# generic_maxi_speed_1.net
KiCad netlist of a schematic drawn in EAGLE
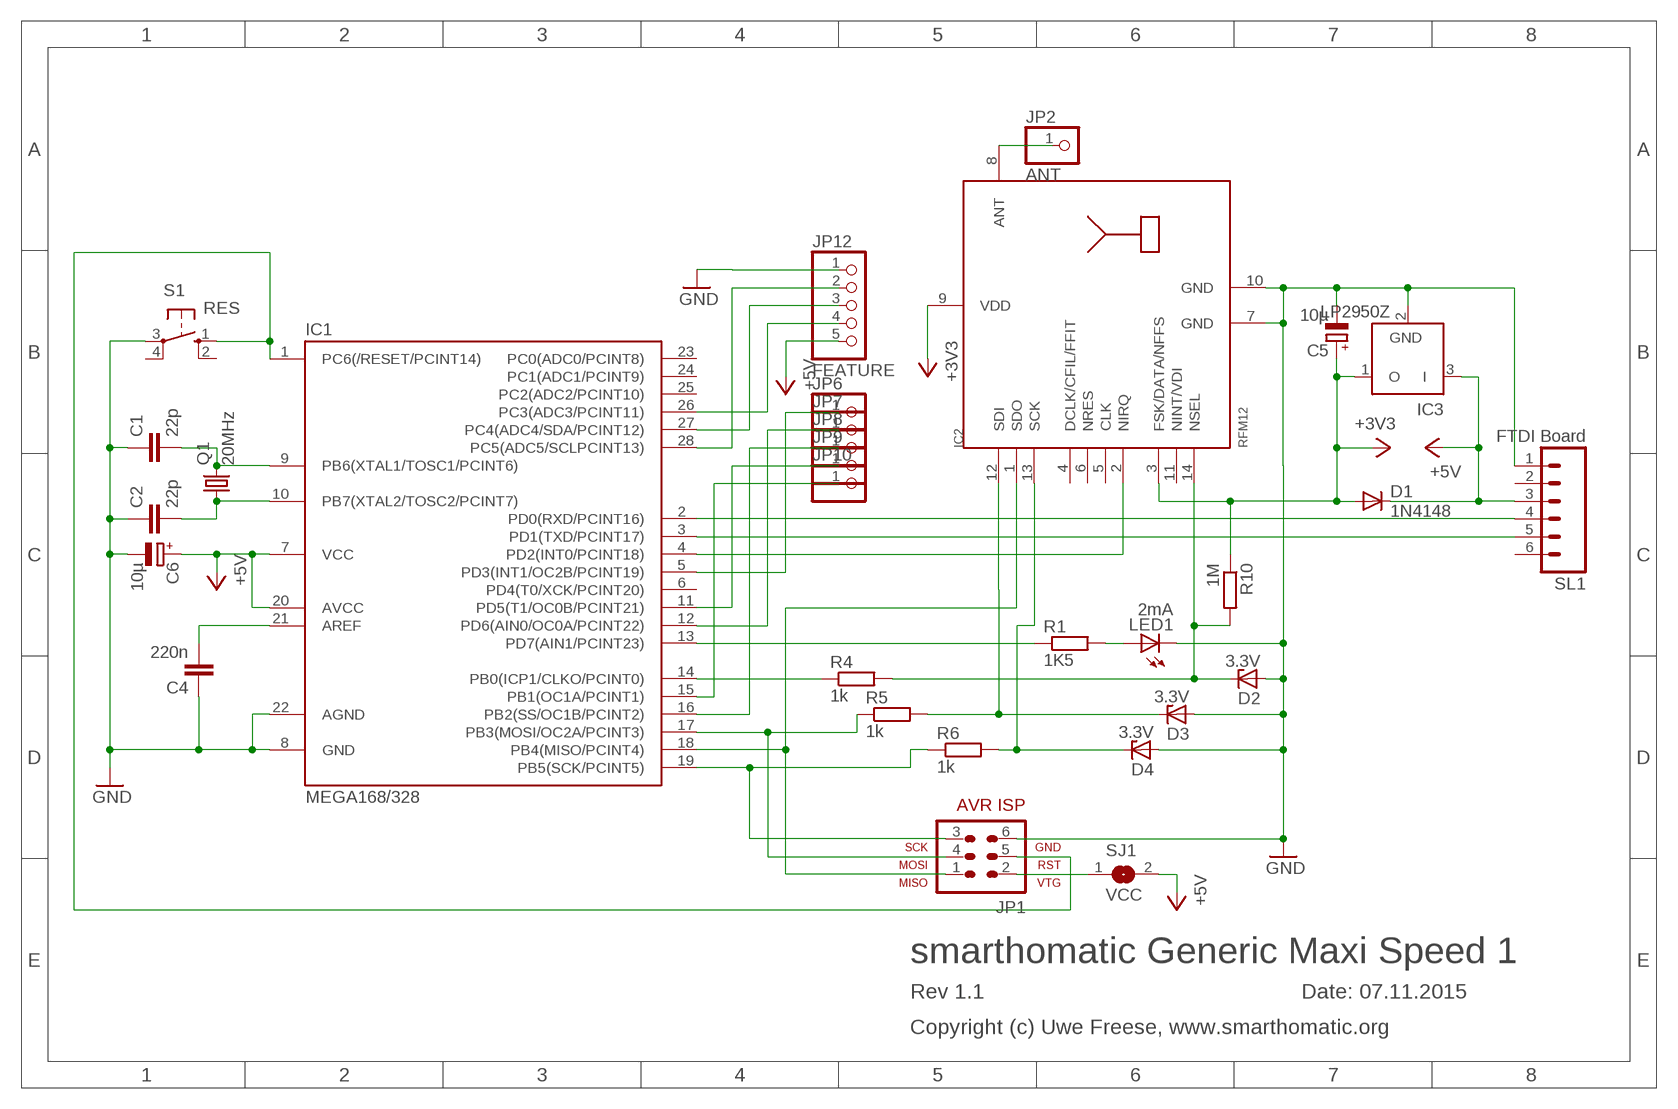
[diagram p0: schematic, sheet 1]

(export (version "E")
  (design (tool "Eeschema 10.0.6"))
  (components
    (comp (ref "C1")
      (value "22p")
      (footprint "eagle-import:C025-024X044")
      (libsource (lib "eagle-import") (part "C-EU025-024X044"))
    )
    (comp (ref "C2")
      (value "22p")
      (footprint "eagle-import:C025-024X044")
      (libsource (lib "eagle-import") (part "C-EU025-024X044"))
    )
    (comp (ref "C4")
      (value "220n")
      (footprint "eagle-import:C025-030X050")
      (libsource (lib "eagle-import") (part "C-EU025-030X050"))
    )
    (comp (ref "C5")
      (value "10µ")
      (footprint "eagle-import:E1,8-4")
      (libsource (lib "eagle-import") (part "CPOL-EUE1.8-4"))
    )
    (comp (ref "C6")
      (value "10µ")
      (footprint "eagle-import:E1,8-4")
      (libsource (lib "eagle-import") (part "CPOL-EUE1.8-4"))
    )
    (comp (ref "D1")
      (value "1N4148")
      (footprint "eagle-import:DO35-7")
      (libsource (lib "eagle-import") (part "1N4148DO35-7"))
    )
    (comp (ref "D2")
      (value "3.3V")
      (footprint "eagle-import:ZDIO-5")
      (libsource (lib "eagle-import") (part "ZENER-DIODEZD-5"))
    )
    (comp (ref "D3")
      (value "3.3V")
      (footprint "eagle-import:ZDIO-5")
      (libsource (lib "eagle-import") (part "ZENER-DIODEZD-5"))
    )
    (comp (ref "D4")
      (value "3.3V")
      (footprint "eagle-import:ZDIO-5")
      (libsource (lib "eagle-import") (part "ZENER-DIODEZD-5"))
    )
    (comp (ref "IC1")
      (value "MEGA168/328")
      (footprint "eagle-import:DIL28-3")
      (libsource (lib "eagle-import") (part "MEGA48/88/168-PU"))
    )
    (comp (ref "IC2")
      (value "RFM12")
      (footprint "eagle-import:RFM")
      (libsource (lib "eagle-import") (part "RFM12"))
    )
    (comp (ref "IC3")
      (value "LP2950Z")
      (footprint "eagle-import:TO92")
      (libsource (lib "eagle-import") (part "LP2950Z"))
    )
    (comp (ref "JP1")
      (value "AVR-ISP-6")
      (footprint "eagle-import:AVR-ISP-6")
      (libsource (lib "eagle-import") (part "AVR-ISP-6"))
    )
    (comp (ref "JP2")
      (value "ANT")
      (footprint "eagle-import:1X01")
      (libsource (lib "eagle-import") (part "PINHD-1X1"))
    )
    (comp (ref "JP6")
      (value "PINHD-1X1")
      (footprint "eagle-import:1X01")
      (libsource (lib "eagle-import") (part "PINHD-1X1"))
    )
    (comp (ref "JP7")
      (value "PINHD-1X1")
      (footprint "eagle-import:1X01")
      (libsource (lib "eagle-import") (part "PINHD-1X1"))
    )
    (comp (ref "JP8")
      (value "PINHD-1X1")
      (footprint "eagle-import:1X01")
      (libsource (lib "eagle-import") (part "PINHD-1X1"))
    )
    (comp (ref "JP9")
      (value "PINHD-1X1")
      (footprint "eagle-import:1X01")
      (libsource (lib "eagle-import") (part "PINHD-1X1"))
    )
    (comp (ref "JP10")
      (value "PINHD-1X1")
      (footprint "eagle-import:1X01")
      (libsource (lib "eagle-import") (part "PINHD-1X1"))
    )
    (comp (ref "JP12")
      (value "FEATURE")
      (footprint "eagle-import:1X05")
      (libsource (lib "eagle-import") (part "PINHD-1X5"))
    )
    (comp (ref "LED1")
      (value "2mA")
      (footprint "eagle-import:LED3MM")
      (libsource (lib "eagle-import") (part "LED3MM"))
    )
    (comp (ref "Q1")
      (value "20MHz")
      (footprint "eagle-import:HC49_S")
      (libsource (lib "eagle-import") (part "CRYSTALHC49S"))
    )
    (comp (ref "R1")
      (value "1K5")
      (footprint "eagle-import:0207_7")
      (libsource (lib "eagle-import") (part "R-EU_0207/7"))
    )
    (comp (ref "R4")
      (value "1k")
      (footprint "eagle-import:0207_7")
      (libsource (lib "eagle-import") (part "R-EU_0207/7"))
    )
    (comp (ref "R5")
      (value "1k")
      (footprint "eagle-import:0207_7")
      (libsource (lib "eagle-import") (part "R-EU_0207/7"))
    )
    (comp (ref "R6")
      (value "1k")
      (footprint "eagle-import:0207_7")
      (libsource (lib "eagle-import") (part "R-EU_0207/7"))
    )
    (comp (ref "R10")
      (value "1M")
      (footprint "eagle-import:0207_7")
      (libsource (lib "eagle-import") (part "R-EU_0207/7"))
    )
    (comp (ref "S1")
      (value "RES")
      (footprint "eagle-import:B3F-10XX")
      (fields (field (name "MPN") "B3F-1000"))
      (libsource (lib "eagle-import") (part "10-XX"))
    )
    (comp (ref "SJ1")
      (value "VCC")
      (footprint "eagle-import:SJ")
      (libsource (lib "eagle-import") (part "SJ"))
    )
    (comp (ref "SL1")
      (value "FTDI Board")
      (footprint "eagle-import:06P")
      (libsource (lib "eagle-import") (part "M06"))
    )
  )
  (nets
    (net (code "1") (name "+3V3") (class "Default")
      (node (ref "C5") (pin "+") (pinfunction "+_+") (pintype "passive"))
      (node (ref "D1") (pin "A") (pinfunction "A_A") (pintype "passive"))
      (node (ref "IC2") (pin "3") (pinfunction "FSK/DATA/NFFS_3") (pintype "bidirectional"))
      (node (ref "IC2") (pin "9") (pinfunction "VDD_9") (pintype "power_in"))
      (node (ref "IC3") (pin "1") (pinfunction "O_1") (pintype "input"))
      (node (ref "R10") (pin "1") (pinfunction "1_1") (pintype "passive"))
    )
    (net (code "2") (name "+5V") (class "Default")
      (node (ref "C6") (pin "+") (pinfunction "+_+") (pintype "passive"))
      (node (ref "D1") (pin "C") (pinfunction "C_C") (pintype "passive"))
      (node (ref "IC1") (pin "20") (pinfunction "AVCC_20") (pintype "passive"))
      (node (ref "IC1") (pin "7") (pinfunction "VCC_7") (pintype "power_in"))
      (node (ref "IC3") (pin "3") (pinfunction "I_3") (pintype "input"))
      (node (ref "JP12") (pin "5") (pinfunction "5_5") (pintype "passive"))
      (node (ref "SJ1") (pin "2") (pinfunction "2_2") (pintype "passive"))
      (node (ref "SL1") (pin "3") (pinfunction "3_3") (pintype "passive"))
    )
    (net (code "3") (name "GND") (class "Default")
      (node (ref "C1") (pin "1") (pinfunction "1_1") (pintype "passive"))
      (node (ref "C2") (pin "1") (pinfunction "1_1") (pintype "passive"))
      (node (ref "C4") (pin "1") (pinfunction "1_1") (pintype "passive"))
      (node (ref "C5") (pin "-") (pinfunction "-_-") (pintype "passive"))
      (node (ref "C6") (pin "-") (pinfunction "-_-") (pintype "passive"))
      (node (ref "D2") (pin "A") (pinfunction "A_A") (pintype "passive"))
      (node (ref "D3") (pin "A") (pinfunction "A_A") (pintype "passive"))
      (node (ref "D4") (pin "A") (pinfunction "A_A") (pintype "passive"))
      (node (ref "IC1") (pin "22") (pinfunction "AGND_22") (pintype "power_in"))
      (node (ref "IC1") (pin "8") (pinfunction "GND_8") (pintype "power_in"))
      (node (ref "IC2") (pin "10") (pinfunction "GND_10") (pintype "power_in"))
      (node (ref "IC2") (pin "7") (pinfunction "GND_7") (pintype "power_in"))
      (node (ref "IC3") (pin "2") (pinfunction "GND_2") (pintype "power_in"))
      (node (ref "JP1") (pin "6") (pinfunction "6_6") (pintype "passive"))
      (node (ref "JP12") (pin "1") (pinfunction "1_1") (pintype "passive"))
      (node (ref "LED1") (pin "K") (pinfunction "C_K") (pintype "passive"))
      (node (ref "S1") (pin "3") (pinfunction "P_3") (pintype "passive"))
      (node (ref "SL1") (pin "1") (pinfunction "1_1") (pintype "passive"))
    )
    (net (code "4") (name "Net-(IC1-AREF)") (class "Default")
      (node (ref "C4") (pin "2") (pinfunction "2_2") (pintype "passive"))
      (node (ref "IC1") (pin "21") (pinfunction "AREF_21") (pintype "passive"))
    )
    (net (code "5") (name "Net-(IC1-PB0(ICP1{slash}CLKO{slash}PCINT0))") (class "Default")
      (node (ref "IC1") (pin "14") (pinfunction "PB0(ICP1/CLKO/PCINT0)_14") (pintype "bidirectional"))
      (node (ref "R4") (pin "1") (pinfunction "1_1") (pintype "passive"))
    )
    (net (code "6") (name "Net-(IC1-PB1(OC1A{slash}PCINT1))") (class "Default")
      (node (ref "IC1") (pin "15") (pinfunction "PB1(OC1A/PCINT1)_15") (pintype "bidirectional"))
      (node (ref "JP10") (pin "1") (pinfunction "1_1") (pintype "passive"))
    )
    (net (code "7") (name "Net-(IC1-PB2(SS{slash}OC1B{slash}PCINT2))") (class "Default")
      (node (ref "IC1") (pin "16") (pinfunction "PB2(SS/OC1B/PCINT2)_16") (pintype "bidirectional"))
      (node (ref "JP8") (pin "1") (pinfunction "1_1") (pintype "passive"))
    )
    (net (code "8") (name "Net-(IC1-PB3(MOSI{slash}OC2A{slash}PCINT3))") (class "Default")
      (node (ref "IC1") (pin "17") (pinfunction "PB3(MOSI/OC2A/PCINT3)_17") (pintype "bidirectional"))
      (node (ref "JP1") (pin "4") (pinfunction "4_4") (pintype "passive"))
      (node (ref "R5") (pin "1") (pinfunction "1_1") (pintype "passive"))
    )
    (net (code "9") (name "Net-(IC1-PB4(MISO{slash}PCINT4))") (class "Default")
      (node (ref "IC1") (pin "18") (pinfunction "PB4(MISO/PCINT4)_18") (pintype "bidirectional"))
      (node (ref "IC2") (pin "1") (pinfunction "SDO_1") (pintype "bidirectional"))
      (node (ref "JP1") (pin "1") (pinfunction "1_1") (pintype "passive"))
    )
    (net (code "10") (name "Net-(IC1-PB5(SCK{slash}PCINT5))") (class "Default")
      (node (ref "IC1") (pin "19") (pinfunction "PB5(SCK/PCINT5)_19") (pintype "bidirectional"))
      (node (ref "JP1") (pin "3") (pinfunction "3_3") (pintype "passive"))
      (node (ref "R6") (pin "1") (pinfunction "1_1") (pintype "passive"))
    )
    (net (code "11") (name "Net-(IC1-PB6(XTAL1{slash}TOSC1{slash}PCINT6))") (class "Default")
      (node (ref "C1") (pin "2") (pinfunction "2_2") (pintype "passive"))
      (node (ref "IC1") (pin "9") (pinfunction "PB6(XTAL1/TOSC1/PCINT6)_9") (pintype "bidirectional"))
      (node (ref "Q1") (pin "2") (pinfunction "2_2") (pintype "passive"))
    )
    (net (code "12") (name "Net-(IC1-PB7(XTAL2{slash}TOSC2{slash}PCINT7))") (class "Default")
      (node (ref "C2") (pin "2") (pinfunction "2_2") (pintype "passive"))
      (node (ref "IC1") (pin "10") (pinfunction "PB7(XTAL2/TOSC2/PCINT7)_10") (pintype "bidirectional"))
      (node (ref "Q1") (pin "1") (pinfunction "1_1") (pintype "passive"))
    )
    (net (code "13") (name "Net-(IC1-PC3(ADC3{slash}PCINT11))") (class "Default")
      (node (ref "IC1") (pin "26") (pinfunction "PC3(ADC3/PCINT11)_26") (pintype "bidirectional"))
      (node (ref "JP12") (pin "4") (pinfunction "4_4") (pintype "passive"))
    )
    (net (code "14") (name "Net-(IC1-PC4(ADC4{slash}SDA{slash}PCINT12))") (class "Default")
      (node (ref "IC1") (pin "27") (pinfunction "PC4(ADC4/SDA/PCINT12)_27") (pintype "bidirectional"))
      (node (ref "JP12") (pin "3") (pinfunction "3_3") (pintype "passive"))
    )
    (net (code "15") (name "Net-(IC1-PC5(ADC5{slash}SCLPCINT13))") (class "Default")
      (node (ref "IC1") (pin "28") (pinfunction "PC5(ADC5/SCLPCINT13)_28") (pintype "bidirectional"))
      (node (ref "JP12") (pin "2") (pinfunction "2_2") (pintype "passive"))
    )
    (net (code "16") (name "Net-(IC1-PC6({slash}RESET{slash}PCINT14))") (class "Default")
      (node (ref "IC1") (pin "1") (pinfunction "PC6(/RESET/PCINT14)_1") (pintype "bidirectional"))
      (node (ref "JP1") (pin "5") (pinfunction "5_5") (pintype "passive"))
      (node (ref "S1") (pin "1") (pinfunction "S_1") (pintype "passive"))
    )
    (net (code "17") (name "Net-(IC1-PD0(RXD{slash}PCINT16))") (class "Default")
      (node (ref "IC1") (pin "2") (pinfunction "PD0(RXD/PCINT16)_2") (pintype "bidirectional"))
      (node (ref "SL1") (pin "4") (pinfunction "4_4") (pintype "passive"))
    )
    (net (code "18") (name "Net-(IC1-PD1(TXD{slash}PCINT17))") (class "Default")
      (node (ref "IC1") (pin "3") (pinfunction "PD1(TXD/PCINT17)_3") (pintype "bidirectional"))
      (node (ref "SL1") (pin "5") (pinfunction "5_5") (pintype "passive"))
    )
    (net (code "19") (name "Net-(IC1-PD2(INT0{slash}PCINT18))") (class "Default")
      (node (ref "IC1") (pin "4") (pinfunction "PD2(INT0/PCINT18)_4") (pintype "bidirectional"))
      (node (ref "IC2") (pin "2") (pinfunction "NIRQ_2") (pintype "bidirectional"))
    )
    (net (code "20") (name "Net-(IC1-PD3(INT1{slash}OC2B{slash}PCINT19))") (class "Default")
      (node (ref "IC1") (pin "5") (pinfunction "PD3(INT1/OC2B/PCINT19)_5") (pintype "bidirectional"))
      (node (ref "JP6") (pin "1") (pinfunction "1_1") (pintype "passive"))
    )
    (net (code "21") (name "Net-(IC1-PD5(T1{slash}OC0B{slash}PCINT21))") (class "Default")
      (node (ref "IC1") (pin "11") (pinfunction "PD5(T1/OC0B/PCINT21)_11") (pintype "bidirectional"))
      (node (ref "JP9") (pin "1") (pinfunction "1_1") (pintype "passive"))
    )
    (net (code "22") (name "Net-(IC1-PD6(AIN0{slash}OC0A{slash}PCINT22))") (class "Default")
      (node (ref "IC1") (pin "12") (pinfunction "PD6(AIN0/OC0A/PCINT22)_12") (pintype "bidirectional"))
      (node (ref "JP7") (pin "1") (pinfunction "1_1") (pintype "passive"))
    )
    (net (code "23") (name "Net-(IC1-PD7(AIN1{slash}PCINT23))") (class "Default")
      (node (ref "IC1") (pin "13") (pinfunction "PD7(AIN1/PCINT23)_13") (pintype "bidirectional"))
      (node (ref "R1") (pin "1") (pinfunction "1_1") (pintype "passive"))
    )
    (net (code "24") (name "Net-(IC2-ANT)") (class "Default")
      (node (ref "IC2") (pin "8") (pinfunction "ANT_8") (pintype "output"))
      (node (ref "JP2") (pin "1") (pinfunction "1_1") (pintype "passive"))
    )
    (net (code "25") (name "Net-(IC2-NSEL)") (class "Default")
      (node (ref "D2") (pin "C") (pinfunction "C_C") (pintype "passive"))
      (node (ref "IC2") (pin "14") (pinfunction "NSEL_14") (pintype "bidirectional"))
      (node (ref "R10") (pin "2") (pinfunction "2_2") (pintype "passive"))
      (node (ref "R4") (pin "2") (pinfunction "2_2") (pintype "passive"))
    )
    (net (code "26") (name "Net-(IC2-SCK)") (class "Default")
      (node (ref "D4") (pin "C") (pinfunction "C_C") (pintype "passive"))
      (node (ref "IC2") (pin "13") (pinfunction "SCK_13") (pintype "bidirectional"))
      (node (ref "R6") (pin "2") (pinfunction "2_2") (pintype "passive"))
    )
    (net (code "27") (name "Net-(IC2-SDI)") (class "Default")
      (node (ref "D3") (pin "C") (pinfunction "C_C") (pintype "passive"))
      (node (ref "IC2") (pin "12") (pinfunction "SDI_12") (pintype "bidirectional"))
      (node (ref "R5") (pin "2") (pinfunction "2_2") (pintype "passive"))
    )
    (net (code "28") (name "Net-(JP1-Pad2)") (class "Default")
      (node (ref "JP1") (pin "2") (pinfunction "2_2") (pintype "passive"))
      (node (ref "SJ1") (pin "1") (pinfunction "1_1") (pintype "passive"))
    )
    (net (code "29") (name "Net-(LED1-PadA)") (class "Default")
      (node (ref "LED1") (pin "A") (pinfunction "A_A") (pintype "passive"))
      (node (ref "R1") (pin "2") (pinfunction "2_2") (pintype "passive"))
    )
    (net (code "30") (name "unconnected-(IC1-PC0(ADC0{slash}PCINT8)-Pad23)") (class "Default")
      (node (ref "IC1") (pin "23") (pinfunction "PC0(ADC0/PCINT8)_23") (pintype "bidirectional"))
    )
    (net (code "31") (name "unconnected-(IC1-PC1(ADC1{slash}PCINT9)-Pad24)") (class "Default")
      (node (ref "IC1") (pin "24") (pinfunction "PC1(ADC1/PCINT9)_24") (pintype "bidirectional"))
    )
    (net (code "32") (name "unconnected-(IC1-PC2(ADC2{slash}PCINT10)-Pad25)") (class "Default")
      (node (ref "IC1") (pin "25") (pinfunction "PC2(ADC2/PCINT10)_25") (pintype "bidirectional"))
    )
    (net (code "33") (name "unconnected-(IC1-PD4(T0{slash}XCK{slash}PCINT20)-Pad6)") (class "Default")
      (node (ref "IC1") (pin "6") (pinfunction "PD4(T0/XCK/PCINT20)_6") (pintype "bidirectional"))
    )
    (net (code "34") (name "unconnected-(IC2-CLK-Pad5)") (class "Default")
      (node (ref "IC2") (pin "5") (pinfunction "CLK_5") (pintype "bidirectional"))
    )
    (net (code "35") (name "unconnected-(IC2-DCLK{slash}CFIL{slash}FFIT-Pad4)") (class "Default")
      (node (ref "IC2") (pin "4") (pinfunction "DCLK/CFIL/FFIT_4") (pintype "bidirectional"))
    )
    (net (code "36") (name "unconnected-(IC2-NINT{slash}VDI-Pad11)") (class "Default")
      (node (ref "IC2") (pin "11") (pinfunction "NINT/VDI_11") (pintype "bidirectional"))
    )
    (net (code "37") (name "unconnected-(IC2-NRES-Pad6)") (class "Default")
      (node (ref "IC2") (pin "6") (pinfunction "NRES_6") (pintype "bidirectional"))
    )
    (net (code "38") (name "unconnected-(S1-P1-Pad4)") (class "Default")
      (node (ref "S1") (pin "4") (pinfunction "P1_4") (pintype "passive"))
    )
    (net (code "39") (name "unconnected-(S1-S1-Pad2)") (class "Default")
      (node (ref "S1") (pin "2") (pinfunction "S1_2") (pintype "passive"))
    )
    (net (code "40") (name "unconnected-(SL1-Pad2)") (class "Default")
      (node (ref "SL1") (pin "2") (pinfunction "2_2") (pintype "passive"))
    )
    (net (code "41") (name "unconnected-(SL1-Pad6)") (class "Default")
      (node (ref "SL1") (pin "6") (pinfunction "6_6") (pintype "passive"))
    )
  )
)
